# RealTimeClock.net
KiCad netlist of a schematic drawn in EAGLE
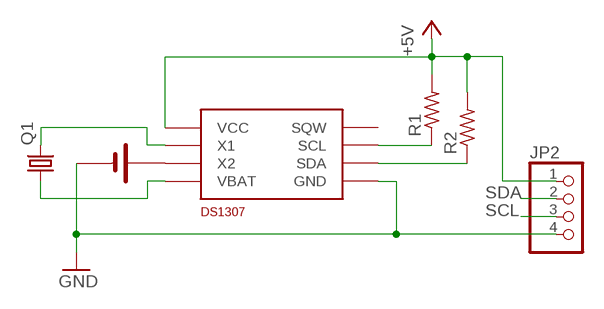
[diagram p0: schematic, sheet 1]

(export (version "E")
  (design (tool "Eeschema 10.0.6"))
  (components
    (comp (ref "CR2032")
      (value "CR2032")
      (footprint "eagle-import:CR2032")
      (libsource (lib "eagle-import") (part "CR2032"))
    )
    (comp (ref "JP2")
      (value "PINHD-1X4/90")
      (footprint "eagle-import:1X04_90")
      (libsource (lib "eagle-import") (part "PINHD-1X4/90"))
    )
    (comp (ref "Q1")
      (value "CRYSTALTC38H")
      (footprint "eagle-import:TC38H")
      (libsource (lib "eagle-import") (part "CRYSTALTC38H"))
    )
    (comp (ref "R1")
      (value "R-US_0204/7")
      (footprint "eagle-import:0204_7")
      (libsource (lib "eagle-import") (part "R-US_0204/7"))
    )
    (comp (ref "R2")
      (value "R-US_0204/7")
      (footprint "eagle-import:0204_7")
      (libsource (lib "eagle-import") (part "R-US_0204/7"))
    )
    (comp (ref "U$1")
      (value "DS1307")
      (footprint "eagle-import:DS1307")
      (libsource (lib "eagle-import") (part "DS1307"))
    )
  )
  (nets
    (net (code "1") (name "+5V") (class "Default")
      (node (ref "JP2") (pin "1") (pinfunction "1_1") (pintype "passive"))
      (node (ref "R1") (pin "2") (pinfunction "2_2") (pintype "passive"))
      (node (ref "R2") (pin "2") (pinfunction "2_2") (pintype "passive"))
      (node (ref "U$1") (pin "VCC") (pinfunction "VCC_VCC") (pintype "bidirectional"))
    )
    (net (code "2") (name "/SCL") (class "Default")
      (node (ref "JP2") (pin "3") (pinfunction "3_3") (pintype "passive"))
      (node (ref "R1") (pin "1") (pinfunction "1_1") (pintype "passive"))
      (node (ref "U$1") (pin "SCL") (pinfunction "SCL_SCL") (pintype "bidirectional"))
    )
    (net (code "3") (name "/SDA") (class "Default")
      (node (ref "JP2") (pin "2") (pinfunction "2_2") (pintype "passive"))
      (node (ref "R2") (pin "1") (pinfunction "1_1") (pintype "passive"))
      (node (ref "U$1") (pin "SDA") (pinfunction "SDA_SDA") (pintype "bidirectional"))
    )
    (net (code "4") (name "GND") (class "Default")
      (node (ref "CR2032") (pin "VCC") (pinfunction "VCC_VCC") (pintype "bidirectional"))
      (node (ref "JP2") (pin "4") (pinfunction "4_4") (pintype "passive"))
      (node (ref "U$1") (pin "GND") (pinfunction "GND_GND") (pintype "bidirectional"))
    )
    (net (code "5") (name "Net-(CR2032-PadGND)") (class "Default")
      (node (ref "CR2032") (pin "GND") (pinfunction "GND_GND") (pintype "bidirectional"))
      (node (ref "U$1") (pin "X2") (pinfunction "X2_X2") (pintype "bidirectional"))
    )
    (net (code "6") (name "Net-(Q1-Pad1)") (class "Default")
      (node (ref "Q1") (pin "1") (pinfunction "1_1") (pintype "passive"))
      (node (ref "U$1") (pin "VBAT") (pinfunction "VBAT_VBAT") (pintype "bidirectional"))
    )
    (net (code "7") (name "Net-(Q1-Pad2)") (class "Default")
      (node (ref "Q1") (pin "2") (pinfunction "2_2") (pintype "passive"))
      (node (ref "U$1") (pin "X1") (pinfunction "X1_X1") (pintype "bidirectional"))
    )
    (net (code "8") (name "unconnected-(U$1-PadSQW)") (class "Default")
      (node (ref "U$1") (pin "SQW") (pinfunction "SQW_SQW") (pintype "bidirectional"))
    )
  )
)
